# LiPo_Drop_Charger_v_6_ATtiny85_--_Dual_M.net
KiCad netlist of a schematic drawn in EAGLE
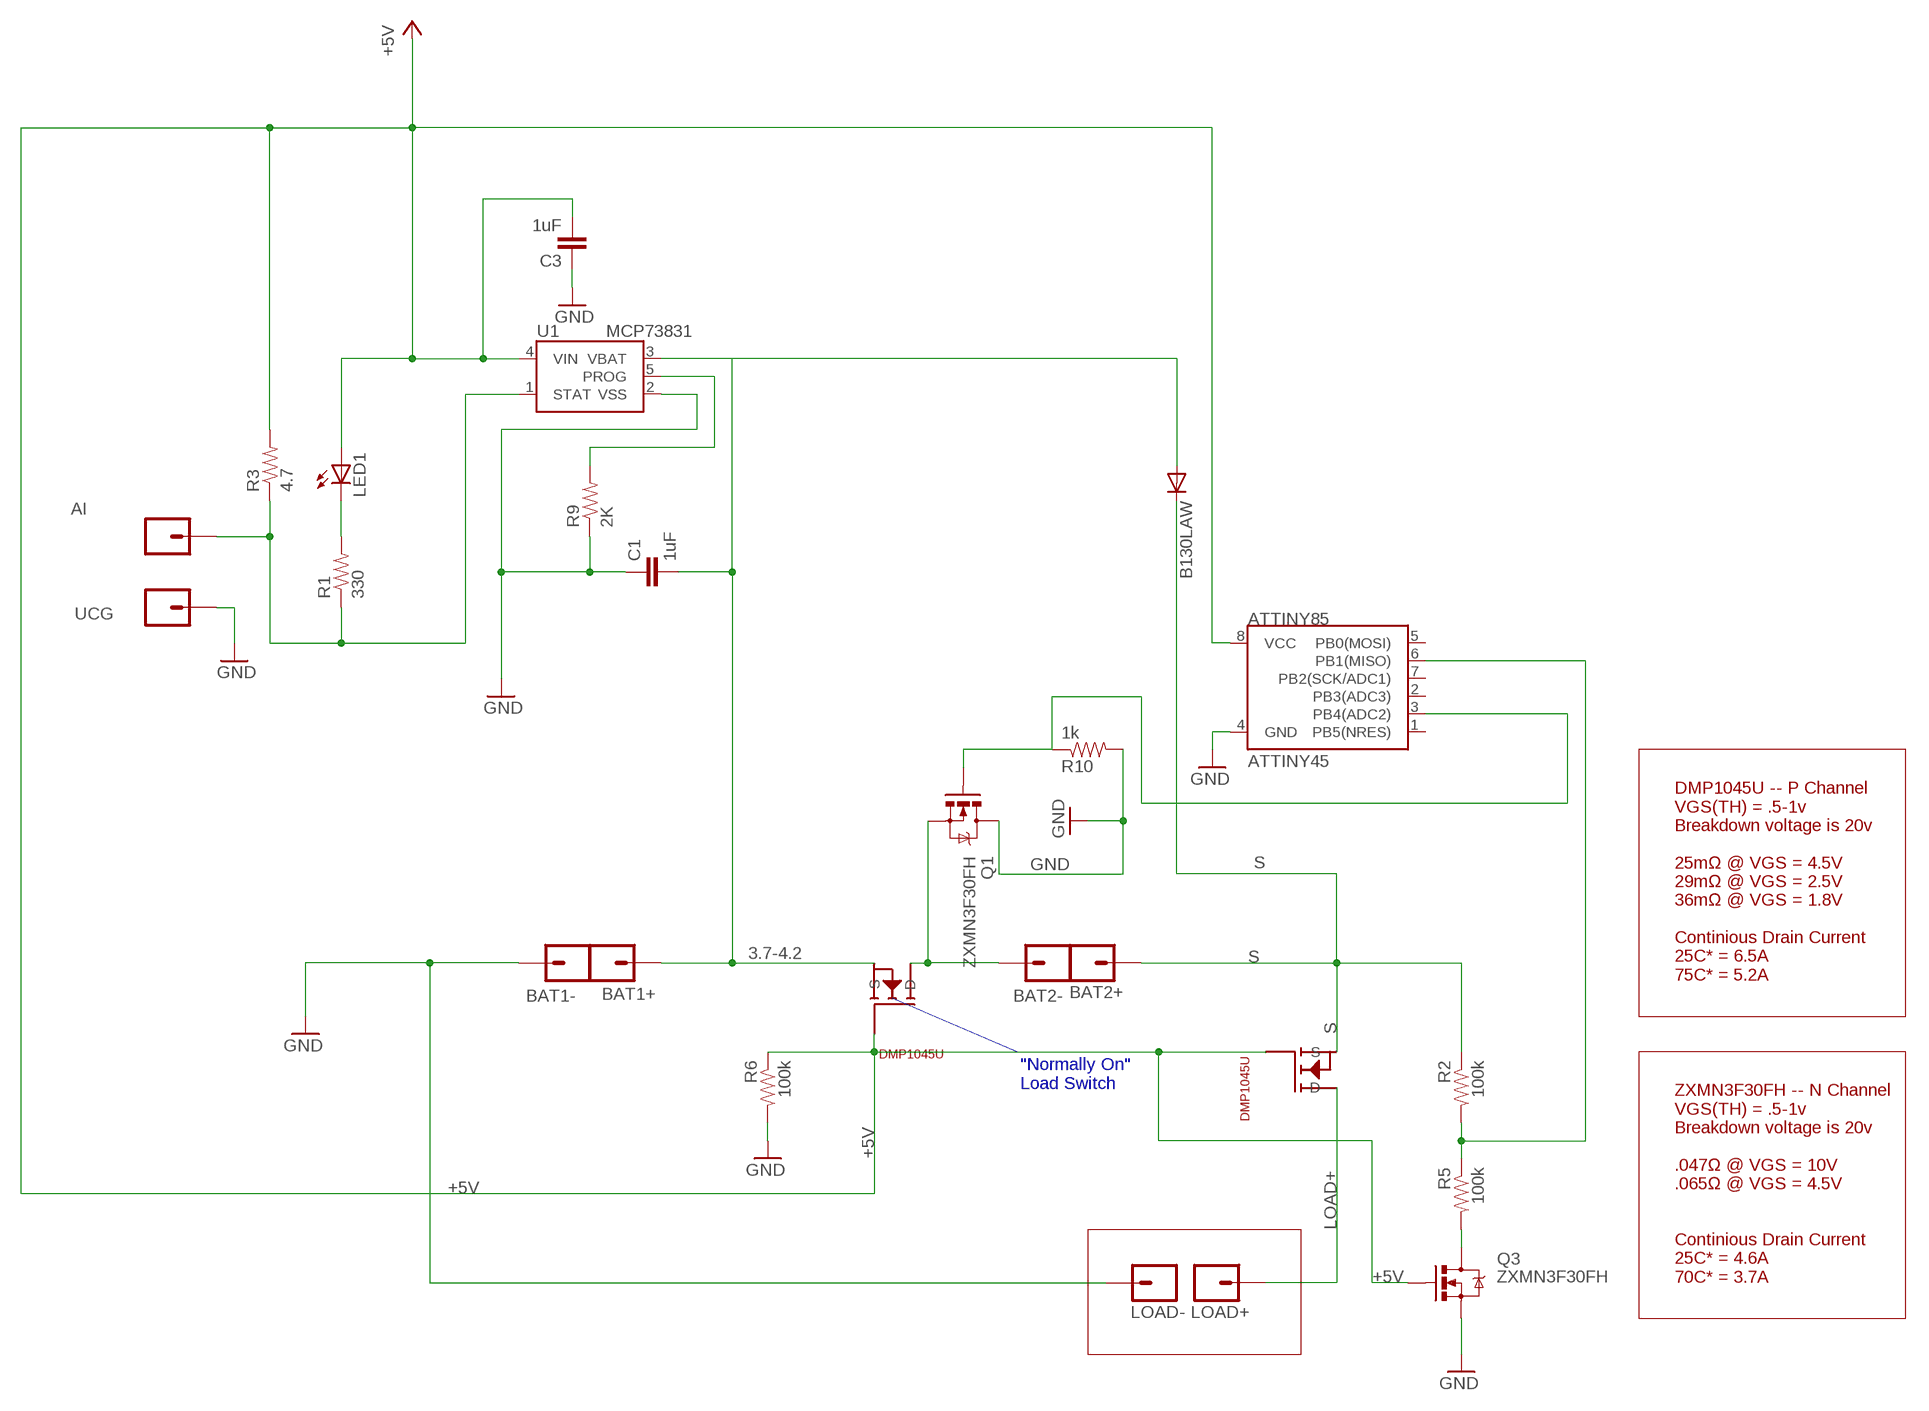
[diagram p0: schematic, sheet 1]

(export (version "E")
  (design (tool "Eeschema 10.0.6"))
  (components
    (comp (ref "AI")
      (value "M01PTH")
      (footprint "eagle-import:1X01")
      (libsource (lib "eagle-import") (part "M01PTH"))
    )
    (comp (ref "ATTINY85")
      (value "ATTINY45")
      (footprint "eagle-import:SO08-EIAJ")
      (libsource (lib "eagle-import") (part "ATTINY45"))
    )
    (comp (ref "B130LAW")
      (value "DIODE-SOD123")
      (footprint "eagle-import:SOD123")
      (libsource (lib "eagle-import") (part "DIODE-SOD123"))
    )
    (comp (ref "BAT1+")
      (value "M01PTH")
      (footprint "eagle-import:1X01")
      (libsource (lib "eagle-import") (part "M01PTH"))
    )
    (comp (ref "BAT1-")
      (value "M01PTH")
      (footprint "eagle-import:1X01")
      (libsource (lib "eagle-import") (part "M01PTH"))
    )
    (comp (ref "BAT2+")
      (value "M01PTH")
      (footprint "eagle-import:1X01")
      (libsource (lib "eagle-import") (part "M01PTH"))
    )
    (comp (ref "BAT2-")
      (value "M01PTH")
      (footprint "eagle-import:1X01")
      (libsource (lib "eagle-import") (part "M01PTH"))
    )
    (comp (ref "C1")
      (value "1uF")
      (footprint "eagle-import:0805")
      (libsource (lib "eagle-import") (part "CAP0805"))
    )
    (comp (ref "C3")
      (value "1uF")
      (footprint "eagle-import:0805")
      (libsource (lib "eagle-import") (part "CAP0805"))
    )
    (comp (ref "LED1")
      (value "LEDCHIP-LED0603")
      (footprint "eagle-import:CHIP-LED0603")
      (libsource (lib "eagle-import") (part "LEDCHIP-LED0603"))
    )
    (comp (ref "LOAD+")
      (value "M01PTH")
      (footprint "eagle-import:1X01")
      (libsource (lib "eagle-import") (part "M01PTH"))
    )
    (comp (ref "LOAD-")
      (value "M01PTH")
      (footprint "eagle-import:1X01")
      (libsource (lib "eagle-import") (part "M01PTH"))
    )
    (comp (ref "Q1")
      (value "ZXMN3F30FH")
      (footprint "eagle-import:SOT23-3")
      (libsource (lib "eagle-import") (part "MOSFET-NCHANNELSMD"))
    )
    (comp (ref "Q3")
      (value "ZXMN3F30FH")
      (footprint "eagle-import:SOT23-3")
      (libsource (lib "eagle-import") (part "MOSFET-NCHANNELSMD"))
    )
    (comp (ref "R1")
      (value "330")
      (footprint "eagle-import:0805")
      (libsource (lib "eagle-import") (part "RESISTOR0805-RES"))
    )
    (comp (ref "R2")
      (value "100k")
      (footprint "eagle-import:0805")
      (libsource (lib "eagle-import") (part "RESISTOR0805-RES"))
    )
    (comp (ref "R3")
      (value "4.7")
      (footprint "eagle-import:0805")
      (libsource (lib "eagle-import") (part "RESISTOR0805-RES"))
    )
    (comp (ref "R5")
      (value "100k")
      (footprint "eagle-import:0805")
      (libsource (lib "eagle-import") (part "RESISTOR0805-RES"))
    )
    (comp (ref "R6")
      (value "100k")
      (footprint "eagle-import:0805")
      (libsource (lib "eagle-import") (part "RESISTOR0805-RES"))
    )
    (comp (ref "R9")
      (value "2K")
      (footprint "eagle-import:0805")
      (libsource (lib "eagle-import") (part "RESISTOR0805-RES"))
    )
    (comp (ref "R10")
      (value "1k")
      (footprint "eagle-import:0805")
      (libsource (lib "eagle-import") (part "RESISTOR0805-RES"))
    )
    (comp (ref "U$1")
      (value "DMP1045U")
      (footprint "eagle-import:SOT-23")
      (libsource (lib "eagle-import") (part "DMP1045U"))
    )
    (comp (ref "U$2")
      (value "DMP1045U")
      (footprint "eagle-import:SOT-23")
      (libsource (lib "eagle-import") (part "DMP1045U"))
    )
    (comp (ref "U1")
      (value "MCP73831")
      (footprint "eagle-import:SOT23-5")
      (libsource (lib "eagle-import") (part "MCP73831"))
    )
    (comp (ref "UCG")
      (value "M01PTH")
      (footprint "eagle-import:1X01")
      (libsource (lib "eagle-import") (part "M01PTH"))
    )
  )
  (nets
    (net (code "1") (name "+5V") (class "Default")
      (node (ref "ATTINY85") (pin "8") (pinfunction "VCC_8") (pintype "bidirectional"))
      (node (ref "C3") (pin "2") (pinfunction "2_2") (pintype "passive"))
      (node (ref "LED1") (pin "A") (pinfunction "A_A") (pintype "passive"))
      (node (ref "Q3") (pin "1") (pinfunction "G_1") (pintype "passive"))
      (node (ref "R3") (pin "2") (pinfunction "2_2") (pintype "passive"))
      (node (ref "R6") (pin "1") (pinfunction "1_1") (pintype "passive"))
      (node (ref "U$1") (pin "1") (pinfunction "G_1") (pintype "power_in"))
      (node (ref "U$2") (pin "1") (pinfunction "G_1") (pintype "power_in"))
      (node (ref "U1") (pin "4") (pinfunction "VIN_4") (pintype "power_in"))
    )
    (net (code "2") (name "/LOAD+") (class "Default")
      (node (ref "LOAD+") (pin "1") (pinfunction "1_1") (pintype "passive"))
      (node (ref "U$2") (pin "3") (pinfunction "D_3") (pintype "power_in"))
    )
    (net (code "3") (name "/S") (class "Default")
      (node (ref "B130LAW") (pin "C") (pinfunction "C_C") (pintype "passive"))
      (node (ref "BAT2+") (pin "1") (pinfunction "1_1") (pintype "passive"))
      (node (ref "R2") (pin "1") (pinfunction "1_1") (pintype "passive"))
      (node (ref "U$2") (pin "2") (pinfunction "S_2") (pintype "power_in"))
    )
    (net (code "4") (name "GND") (class "Default")
      (node (ref "ATTINY85") (pin "4") (pinfunction "GND_4") (pintype "bidirectional"))
      (node (ref "BAT1-") (pin "1") (pinfunction "1_1") (pintype "passive"))
      (node (ref "C1") (pin "1") (pinfunction "1_1") (pintype "passive"))
      (node (ref "C3") (pin "1") (pinfunction "1_1") (pintype "passive"))
      (node (ref "LOAD-") (pin "1") (pinfunction "1_1") (pintype "passive"))
      (node (ref "Q1") (pin "3") (pinfunction "D_3") (pintype "passive"))
      (node (ref "Q3") (pin "2") (pinfunction "S_2") (pintype "passive"))
      (node (ref "R10") (pin "2") (pinfunction "2_2") (pintype "passive"))
      (node (ref "R6") (pin "2") (pinfunction "2_2") (pintype "passive"))
      (node (ref "R9") (pin "1") (pinfunction "1_1") (pintype "passive"))
      (node (ref "U1") (pin "2") (pinfunction "VSS_2") (pintype "power_in"))
      (node (ref "UCG") (pin "1") (pinfunction "1_1") (pintype "passive"))
    )
    (net (code "5") (name "Net-(ATTINY85-PB1(MISO))") (class "Default")
      (node (ref "ATTINY85") (pin "6") (pinfunction "PB1(MISO)_6") (pintype "bidirectional"))
      (node (ref "R2") (pin "2") (pinfunction "2_2") (pintype "passive"))
      (node (ref "R5") (pin "1") (pinfunction "1_1") (pintype "passive"))
    )
    (net (code "6") (name "Net-(ATTINY85-PB4(ADC2))") (class "Default")
      (node (ref "ATTINY85") (pin "3") (pinfunction "PB4(ADC2)_3") (pintype "bidirectional"))
      (node (ref "Q1") (pin "1") (pinfunction "G_1") (pintype "passive"))
      (node (ref "R10") (pin "1") (pinfunction "1_1") (pintype "passive"))
    )
    (net (code "7") (name "Net-(LED1-PadC)") (class "Default")
      (node (ref "LED1") (pin "C") (pinfunction "C_C") (pintype "passive"))
      (node (ref "R1") (pin "2") (pinfunction "2_2") (pintype "passive"))
    )
    (net (code "8") (name "Net-(Q1-S)") (class "Default")
      (node (ref "BAT2-") (pin "1") (pinfunction "1_1") (pintype "passive"))
      (node (ref "Q1") (pin "2") (pinfunction "S_2") (pintype "passive"))
      (node (ref "U$1") (pin "3") (pinfunction "D_3") (pintype "power_in"))
    )
    (net (code "9") (name "Net-(Q3-D)") (class "Default")
      (node (ref "Q3") (pin "3") (pinfunction "D_3") (pintype "passive"))
      (node (ref "R5") (pin "2") (pinfunction "2_2") (pintype "passive"))
    )
    (net (code "10") (name "Net-(U$1-S)") (class "Default")
      (node (ref "B130LAW") (pin "A") (pinfunction "A_A") (pintype "passive"))
      (node (ref "BAT1+") (pin "1") (pinfunction "1_1") (pintype "passive"))
      (node (ref "C1") (pin "2") (pinfunction "2_2") (pintype "passive"))
      (node (ref "U$1") (pin "2") (pinfunction "S_2") (pintype "power_in"))
      (node (ref "U1") (pin "3") (pinfunction "VBAT_3") (pintype "power_in"))
    )
    (net (code "11") (name "Net-(U1-PROG)") (class "Default")
      (node (ref "R9") (pin "2") (pinfunction "2_2") (pintype "passive"))
      (node (ref "U1") (pin "5") (pinfunction "PROG_5") (pintype "input"))
    )
    (net (code "12") (name "Net-(U1-STAT)") (class "Default")
      (node (ref "AI") (pin "1") (pinfunction "1_1") (pintype "passive"))
      (node (ref "R1") (pin "1") (pinfunction "1_1") (pintype "passive"))
      (node (ref "R3") (pin "1") (pinfunction "1_1") (pintype "passive"))
      (node (ref "U1") (pin "1") (pinfunction "STAT_1") (pintype "output"))
    )
    (net (code "13") (name "unconnected-(ATTINY85-PB0(MOSI)-Pad5)") (class "Default")
      (node (ref "ATTINY85") (pin "5") (pinfunction "PB0(MOSI)_5") (pintype "bidirectional"))
    )
    (net (code "14") (name "unconnected-(ATTINY85-PB2(SCK{slash}ADC1)-Pad7)") (class "Default")
      (node (ref "ATTINY85") (pin "7") (pinfunction "PB2(SCK/ADC1)_7") (pintype "bidirectional"))
    )
    (net (code "15") (name "unconnected-(ATTINY85-PB3(ADC3)-Pad2)") (class "Default")
      (node (ref "ATTINY85") (pin "2") (pinfunction "PB3(ADC3)_2") (pintype "bidirectional"))
    )
    (net (code "16") (name "unconnected-(ATTINY85-PB5(NRES)-Pad1)") (class "Default")
      (node (ref "ATTINY85") (pin "1") (pinfunction "PB5(NRES)_1") (pintype "bidirectional"))
    )
  )
)
